# 17_20.net
KiCad netlist of a schematic drawn in Altium Designer
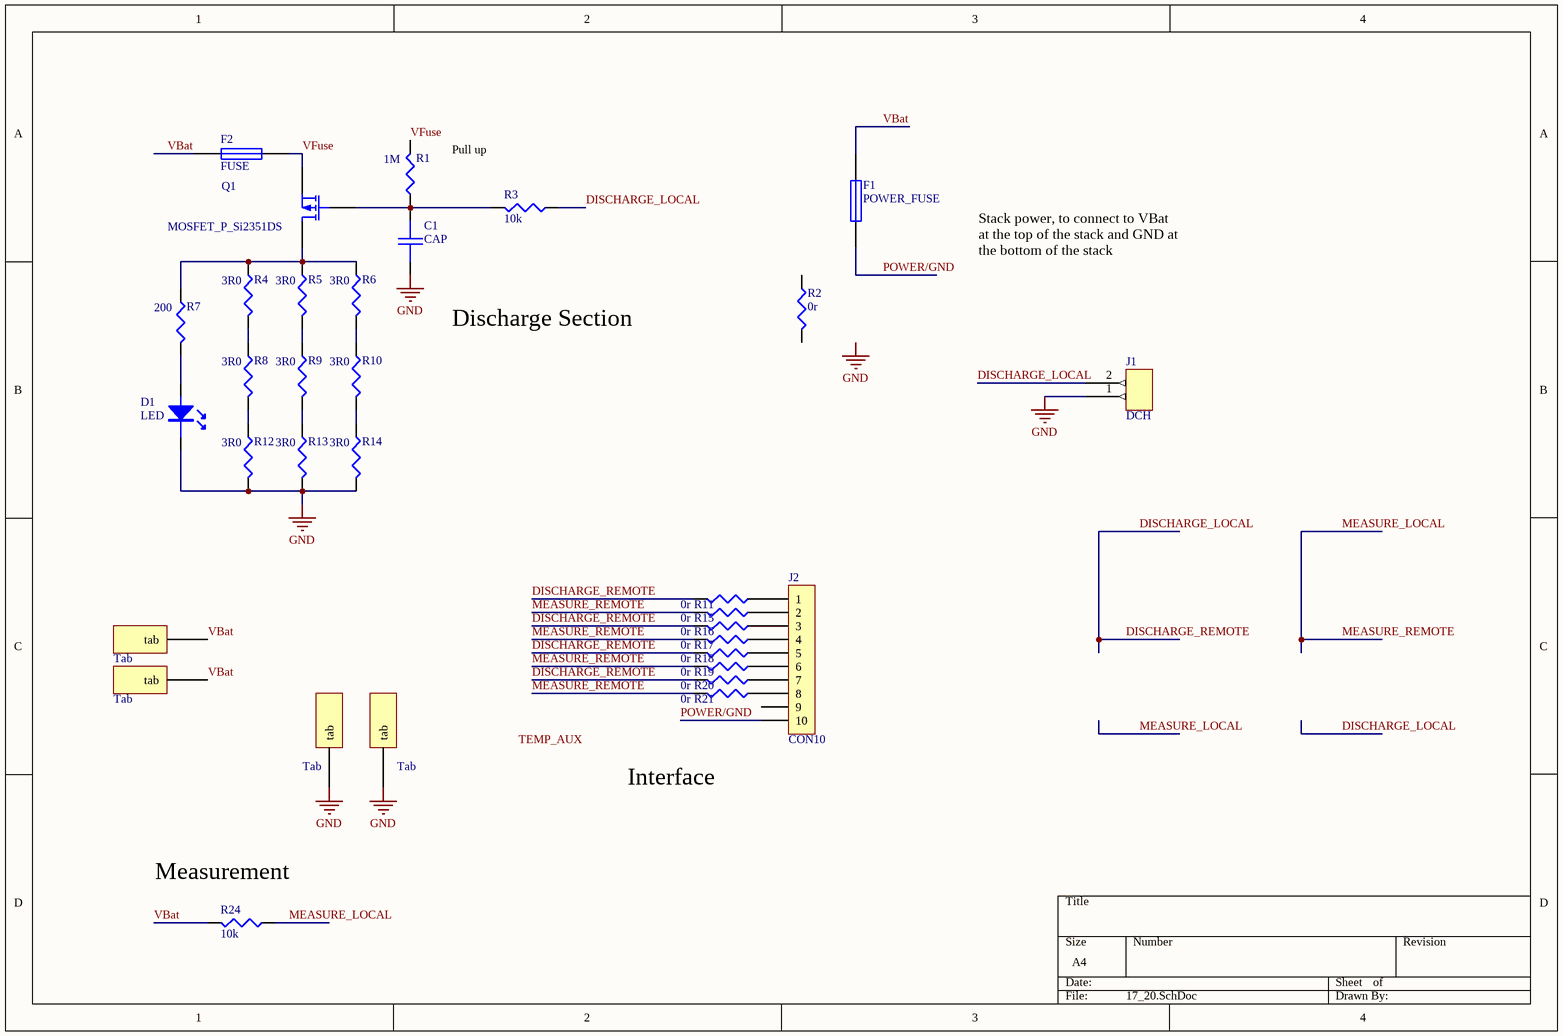
[diagram p0: 17_20.SchDoc]

(export (version "E")
  (design (tool "Eeschema 10.0.6"))
  (components
    (comp (ref "C1")
      (value "CAP")
      (footprint "0603")
      (description "Capacitor")
      (libsource (lib "RCLDQ") (part "CAP"))
    )
    (comp (ref "D1") (value "LED") (footprint "0805LED") (libsource (lib "RCLDQ") (part "LED")))
    (comp (ref "F1")
      (value "POWER_FUSE")
      (footprint "1210")
      (description "Fuse")
      (libsource (lib "Miscellaneous") (part "FUSE"))
    )
    (comp (ref "F2")
      (value "FUSE")
      (footprint "LITTELFUSE-154")
      (description "Fuse")
      (libsource (lib "Miscellaneous") (part "FUSE"))
    )
    (comp (ref "J1") (value "DCH") (footprint "IDC2") (libsource (lib "Connectors") (part "CON2")))
    (comp (ref "J2")
      (value "CON10")
      (footprint "IDC10")
      (description "10 pin, right angle, ribbon con with claws")
      (libsource (lib "Connectors") (part "CON10"))
    )
    (comp (ref "J4") (value "Tab") (footprint "tab_connect") (libsource (lib "") (part "tab_connection_1")))
    (comp (ref "J5") (value "Tab") (footprint "tab_connect") (libsource (lib "") (part "tab_connection_1")))
    (comp (ref "J6") (value "Tab") (footprint "tab_connect") (libsource (lib "BMS") (part "tab_connection")))
    (comp (ref "J7") (value "Tab") (footprint "tab_connect") (libsource (lib "BMS") (part "tab_connection")))
    (comp (ref "Q1")
      (value "MOSFET_P_Si2351DS")
      (footprint "SOT23-3")
      (description "Si2351DS P-Channel MOSFET")
      (fields (field (name "PUBLISHER") "Altium Limited"))
      (libsource (lib "RCLDQ") (part "MOSFET_P_Si2351DS"))
    )
    (comp (ref "R1")
      (value "~")
      (footprint "0603")
      (description "Resistor")
      (fields (field (name "RESISTANCE") "1M"))
      (libsource (lib "RCLDQ") (part "RES1"))
    )
    (comp (ref "R2")
      (value "~")
      (footprint "1206")
      (description "Resistor")
      (fields (field (name "RESISTANCE") "0r"))
      (libsource (lib "RCLDQ") (part "RES1"))
    )
    (comp (ref "R3")
      (value "~")
      (footprint "0603")
      (description "Resistor")
      (fields (field (name "RESISTANCE") "10k"))
      (libsource (lib "RCLDQ") (part "RES1"))
    )
    (comp (ref "R4")
      (value "3R0")
      (footprint "2512")
      (description "Resistor")
      (libsource (lib "RCLDQ") (part "RES1"))
    )
    (comp (ref "R5")
      (value "3R0")
      (footprint "2512")
      (description "Resistor")
      (libsource (lib "RCLDQ") (part "RES1"))
    )
    (comp (ref "R6")
      (value "3R0")
      (footprint "2512")
      (description "Resistor")
      (libsource (lib "RCLDQ") (part "RES1"))
    )
    (comp (ref "R7")
      (value "200")
      (footprint "0603")
      (description "Resistor")
      (libsource (lib "RCLDQ") (part "RES1"))
    )
    (comp (ref "R8")
      (value "3R0")
      (footprint "2512")
      (description "Resistor")
      (libsource (lib "RCLDQ") (part "RES1"))
    )
    (comp (ref "R9")
      (value "3R0")
      (footprint "2512")
      (description "Resistor")
      (libsource (lib "RCLDQ") (part "RES1"))
    )
    (comp (ref "R10")
      (value "3R0")
      (footprint "2512")
      (description "Resistor")
      (libsource (lib "RCLDQ") (part "RES1"))
    )
    (comp (ref "R11")
      (value "~")
      (footprint "0603")
      (description "Resistor")
      (fields (field (name "RESISTANCE") "0r"))
      (libsource (lib "RCLDQ") (part "RES1"))
    )
    (comp (ref "R12")
      (value "3R0")
      (footprint "2512")
      (description "Resistor")
      (libsource (lib "RCLDQ") (part "RES1"))
    )
    (comp (ref "R13")
      (value "3R0")
      (footprint "2512")
      (description "Resistor")
      (libsource (lib "RCLDQ") (part "RES1"))
    )
    (comp (ref "R14")
      (value "3R0")
      (footprint "2512")
      (description "Resistor")
      (libsource (lib "RCLDQ") (part "RES1"))
    )
    (comp (ref "R15")
      (value "~")
      (footprint "0603")
      (description "Resistor")
      (fields (field (name "RESISTANCE") "0r"))
      (libsource (lib "RCLDQ") (part "RES1"))
    )
    (comp (ref "R16")
      (value "~")
      (footprint "0603")
      (description "Resistor")
      (fields (field (name "RESISTANCE") "0r"))
      (libsource (lib "RCLDQ") (part "RES1"))
    )
    (comp (ref "R17")
      (value "~")
      (footprint "0603")
      (description "Resistor")
      (fields (field (name "RESISTANCE") "0r"))
      (libsource (lib "RCLDQ") (part "RES1"))
    )
    (comp (ref "R18")
      (value "~")
      (footprint "0603")
      (description "Resistor")
      (fields (field (name "RESISTANCE") "0r"))
      (libsource (lib "RCLDQ") (part "RES1"))
    )
    (comp (ref "R19")
      (value "~")
      (footprint "0603")
      (description "Resistor")
      (fields (field (name "RESISTANCE") "0r"))
      (libsource (lib "RCLDQ") (part "RES1"))
    )
    (comp (ref "R20")
      (value "~")
      (footprint "0603")
      (description "Resistor")
      (fields (field (name "RESISTANCE") "0r"))
      (libsource (lib "RCLDQ") (part "RES1"))
    )
    (comp (ref "R21")
      (value "~")
      (footprint "0603")
      (description "Resistor")
      (fields (field (name "RESISTANCE") "0r"))
      (libsource (lib "RCLDQ") (part "RES1"))
    )
    (comp (ref "R24")
      (value "~")
      (footprint "0603")
      (description "Resistor")
      (fields (field (name "RESISTANCE") "10k"))
      (libsource (lib "RCLDQ") (part "RES1"))
    )
  )
  (nets
    (net (code "1") (name "/DISCHARGE_LOCAL") (class "Default")
      (node (ref "J1") (pin "2") (pinfunction "2_2") (pintype "output"))
      (node (ref "R11") (pin "2") (pinfunction "2_2") (pintype "passive"))
      (node (ref "R16") (pin "2") (pinfunction "2_2") (pintype "passive"))
      (node (ref "R18") (pin "2") (pinfunction "2_2") (pintype "passive"))
      (node (ref "R20") (pin "2") (pinfunction "2_2") (pintype "passive"))
      (node (ref "R3") (pin "1") (pinfunction "1_1") (pintype "passive"))
    )
    (net (code "2") (name "/MEASURE_LOCAL") (class "Default")
      (node (ref "R15") (pin "2") (pinfunction "2_2") (pintype "passive"))
      (node (ref "R17") (pin "2") (pinfunction "2_2") (pintype "passive"))
      (node (ref "R19") (pin "2") (pinfunction "2_2") (pintype "passive"))
      (node (ref "R21") (pin "2") (pinfunction "2_2") (pintype "passive"))
      (node (ref "R24") (pin "1") (pinfunction "1_1") (pintype "passive"))
    )
    (net (code "3") (name "/POWER{slash}GND") (class "Default")
      (node (ref "F1") (pin "1") (pinfunction "1_1") (pintype "passive"))
      (node (ref "J2") (pin "10") (pinfunction "10_10") (pintype "passive"))
    )
    (net (code "5") (name "/VBat") (class "Default")
      (node (ref "F1") (pin "2") (pinfunction "2_2") (pintype "passive"))
      (node (ref "F2") (pin "1") (pinfunction "1_1") (pintype "passive"))
      (node (ref "J4") (pin "0") (pinfunction "tab_0") (pintype "passive"))
      (node (ref "J5") (pin "0") (pinfunction "tab_0") (pintype "passive"))
      (node (ref "R24") (pin "2") (pinfunction "2_2") (pintype "passive"))
    )
    (net (code "6") (name "/VFuse") (class "Default")
      (node (ref "F2") (pin "2") (pinfunction "2_2") (pintype "passive"))
      (node (ref "Q1") (pin "2") (pinfunction "S_2") (pintype "passive"))
      (node (ref "R1") (pin "2") (pinfunction "2_2") (pintype "passive"))
    )
    (net (code "7") (name "GND") (class "Default")
      (node (ref "C1") (pin "2") (pinfunction "2_2") (pintype "passive"))
      (node (ref "D1") (pin "K") (pinfunction "K_K") (pintype "passive"))
      (node (ref "J1") (pin "1") (pinfunction "1_1") (pintype "output"))
      (node (ref "J6") (pin "0") (pinfunction "tab_0") (pintype "passive"))
      (node (ref "J7") (pin "0") (pinfunction "tab_0") (pintype "passive"))
      (node (ref "R12") (pin "2") (pinfunction "2_2") (pintype "passive"))
      (node (ref "R13") (pin "2") (pinfunction "2_2") (pintype "passive"))
      (node (ref "R14") (pin "2") (pinfunction "2_2") (pintype "passive"))
    )
    (net (code "8") (name "Net-(D1-PadA)") (class "Default")
      (node (ref "D1") (pin "A") (pinfunction "A_A") (pintype "passive"))
      (node (ref "R7") (pin "2") (pinfunction "2_2") (pintype "passive"))
    )
    (net (code "9") (name "Net-(J2-Pad1)") (class "Default")
      (node (ref "J2") (pin "1") (pinfunction "1_1") (pintype "passive"))
      (node (ref "R11") (pin "1") (pinfunction "1_1") (pintype "passive"))
    )
    (net (code "10") (name "Net-(J2-Pad2)") (class "Default")
      (node (ref "J2") (pin "2") (pinfunction "2_2") (pintype "passive"))
      (node (ref "R15") (pin "1") (pinfunction "1_1") (pintype "passive"))
    )
    (net (code "11") (name "Net-(J2-Pad3)") (class "Default")
      (node (ref "J2") (pin "3") (pinfunction "3_3") (pintype "passive"))
      (node (ref "R16") (pin "1") (pinfunction "1_1") (pintype "passive"))
    )
    (net (code "12") (name "Net-(J2-Pad4)") (class "Default")
      (node (ref "J2") (pin "4") (pinfunction "4_4") (pintype "passive"))
      (node (ref "R17") (pin "1") (pinfunction "1_1") (pintype "passive"))
    )
    (net (code "13") (name "Net-(J2-Pad5)") (class "Default")
      (node (ref "J2") (pin "5") (pinfunction "5_5") (pintype "passive"))
      (node (ref "R18") (pin "1") (pinfunction "1_1") (pintype "passive"))
    )
    (net (code "14") (name "Net-(J2-Pad6)") (class "Default")
      (node (ref "J2") (pin "6") (pinfunction "6_6") (pintype "passive"))
      (node (ref "R19") (pin "1") (pinfunction "1_1") (pintype "passive"))
    )
    (net (code "15") (name "Net-(J2-Pad7)") (class "Default")
      (node (ref "J2") (pin "7") (pinfunction "7_7") (pintype "passive"))
      (node (ref "R20") (pin "1") (pinfunction "1_1") (pintype "passive"))
    )
    (net (code "16") (name "Net-(J2-Pad8)") (class "Default")
      (node (ref "J2") (pin "8") (pinfunction "8_8") (pintype "passive"))
      (node (ref "R21") (pin "1") (pinfunction "1_1") (pintype "passive"))
    )
    (net (code "17") (name "Net-(Q1-D)") (class "Default")
      (node (ref "Q1") (pin "3") (pinfunction "D_3") (pintype "passive"))
      (node (ref "R4") (pin "1") (pinfunction "1_1") (pintype "passive"))
      (node (ref "R5") (pin "1") (pinfunction "1_1") (pintype "passive"))
      (node (ref "R6") (pin "1") (pinfunction "1_1") (pintype "passive"))
      (node (ref "R7") (pin "1") (pinfunction "1_1") (pintype "passive"))
    )
    (net (code "18") (name "Net-(Q1-G)") (class "Default")
      (node (ref "C1") (pin "1") (pinfunction "1_1") (pintype "passive"))
      (node (ref "Q1") (pin "1") (pinfunction "G_1") (pintype "passive"))
      (node (ref "R1") (pin "1") (pinfunction "1_1") (pintype "passive"))
      (node (ref "R3") (pin "2") (pinfunction "2_2") (pintype "passive"))
    )
    (net (code "19") (name "Net-(R4-Pad2)") (class "Default")
      (node (ref "R4") (pin "2") (pinfunction "2_2") (pintype "passive"))
      (node (ref "R8") (pin "1") (pinfunction "1_1") (pintype "passive"))
    )
    (net (code "20") (name "Net-(R5-Pad2)") (class "Default")
      (node (ref "R5") (pin "2") (pinfunction "2_2") (pintype "passive"))
      (node (ref "R9") (pin "1") (pinfunction "1_1") (pintype "passive"))
    )
    (net (code "21") (name "Net-(R10-Pad1)") (class "Default")
      (node (ref "R10") (pin "1") (pinfunction "1_1") (pintype "passive"))
      (node (ref "R6") (pin "2") (pinfunction "2_2") (pintype "passive"))
    )
    (net (code "22") (name "Net-(R10-Pad2)") (class "Default")
      (node (ref "R10") (pin "2") (pinfunction "2_2") (pintype "passive"))
      (node (ref "R14") (pin "1") (pinfunction "1_1") (pintype "passive"))
    )
    (net (code "23") (name "Net-(R12-Pad1)") (class "Default")
      (node (ref "R12") (pin "1") (pinfunction "1_1") (pintype "passive"))
      (node (ref "R8") (pin "2") (pinfunction "2_2") (pintype "passive"))
    )
    (net (code "24") (name "Net-(R13-Pad1)") (class "Default")
      (node (ref "R13") (pin "1") (pinfunction "1_1") (pintype "passive"))
      (node (ref "R9") (pin "2") (pinfunction "2_2") (pintype "passive"))
    )
    (net (code "25") (name "unconnected-(J2-Pad9)") (class "Default")
      (node (ref "J2") (pin "9") (pinfunction "9_9") (pintype "passive"))
    )
    (net (code "26") (name "unconnected-(R2-Pad1)") (class "Default")
      (node (ref "R2") (pin "1") (pinfunction "1_1") (pintype "passive"))
    )
    (net (code "27") (name "unconnected-(R2-Pad2)") (class "Default")
      (node (ref "R2") (pin "2") (pinfunction "2_2") (pintype "passive"))
    )
  )
)
